# minidoxs-ctrl-lz.net
KiCad netlist of a schematic drawn in EAGLE
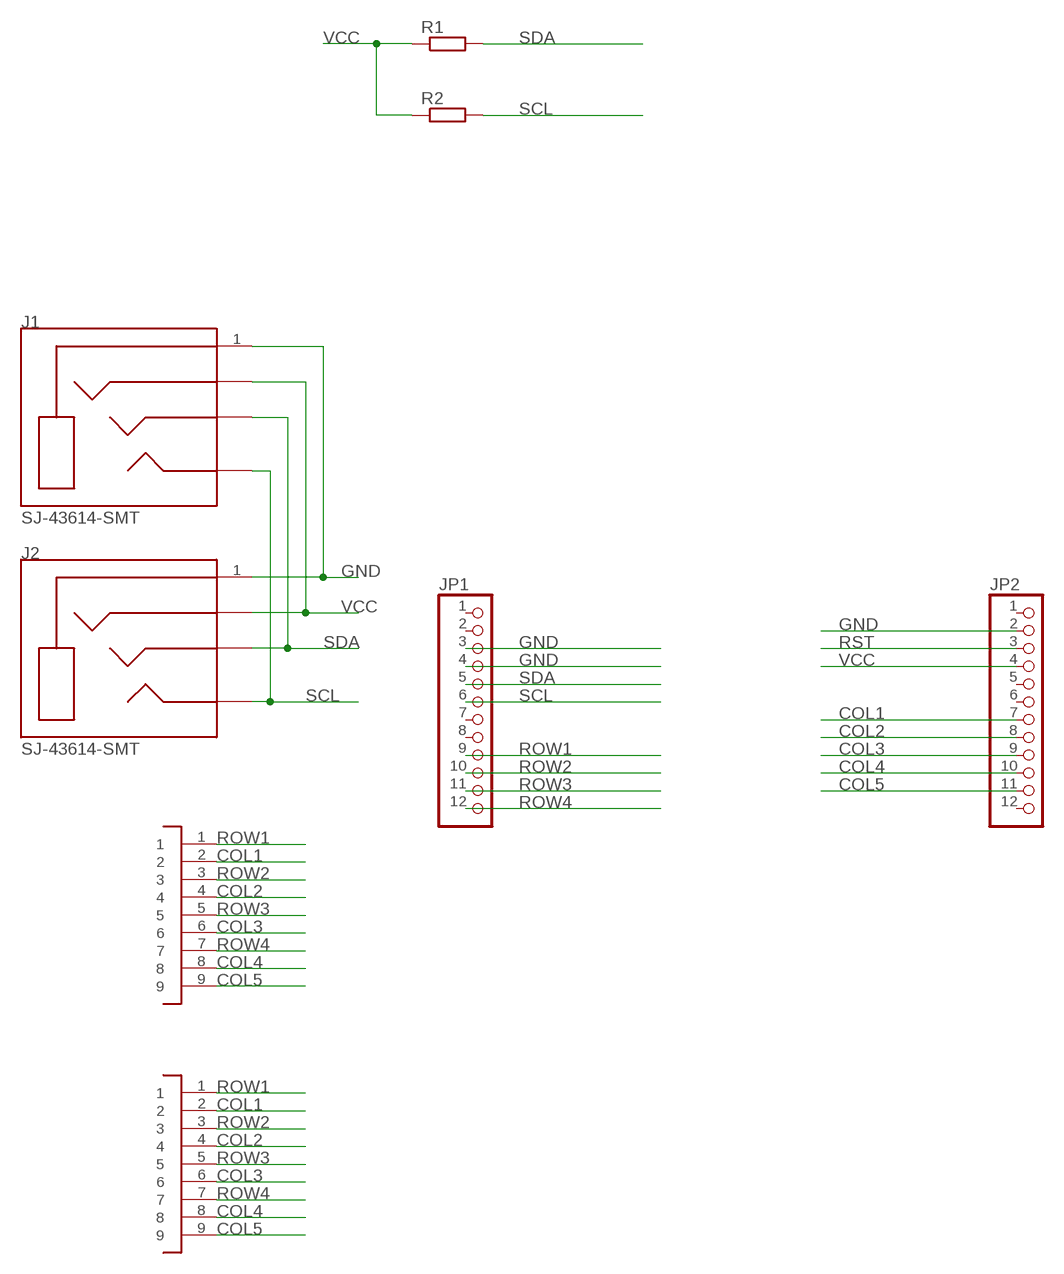
[diagram p0: schematic, sheet 1]

(export (version "E")
  (design (tool "Eeschema 10.0.6"))
  (components
    (comp (ref "J1")
      (value "SJ-43614-SMT")
      (footprint "eagle-import:CUI_SJ-43614-SMT")
      (fields (field (name "MANUFACTURER") "CUI INC"))
      (libsource (lib "eagle-import") (part "SJ-43614-SMT"))
    )
    (comp (ref "J2")
      (value "SJ-43614-SMT")
      (footprint "eagle-import:CUI_SJ-43614-SMT")
      (fields (field (name "MANUFACTURER") "CUI INC"))
      (libsource (lib "eagle-import") (part "SJ-43614-SMT"))
    )
    (comp (ref "JP1")
      (value "PINHD-1X12")
      (footprint "eagle-import:1X12")
      (libsource (lib "eagle-import") (part "PINHD-1X12"))
    )
    (comp (ref "JP2")
      (value "PINHD-1X12")
      (footprint "eagle-import:1X12")
      (libsource (lib "eagle-import") (part "PINHD-1X12"))
    )
    (comp (ref "R1")
      (value "RESISTOR-0603")
      (footprint "eagle-import:R0603")
      (libsource (lib "eagle-import") (part "RESISTOR-0603"))
    )
    (comp (ref "R2")
      (value "RESISTOR-0603")
      (footprint "eagle-import:R0603")
      (libsource (lib "eagle-import") (part "RESISTOR-0603"))
    )
    (comp (ref "U$1")
      (value "HEADER-9X1-2.54")
      (footprint "eagle-import:HEADER-9X1-2.54")
      (libsource (lib "eagle-import") (part "HEADER-9X1-2.54"))
    )
    (comp (ref "U$2")
      (value "HEADER-9X1-2.54")
      (footprint "eagle-import:HEADER-9X1-2.54")
      (libsource (lib "eagle-import") (part "HEADER-9X1-2.54"))
    )
  )
  (nets
    (net (code "1") (name "/COL1") (class "Default")
      (node (ref "JP2") (pin "7") (pinfunction "7_7") (pintype "passive"))
      (node (ref "U$1") (pin "2") (pinfunction "2_2") (pintype "bidirectional"))
      (node (ref "U$2") (pin "2") (pinfunction "2_2") (pintype "bidirectional"))
    )
    (net (code "2") (name "/COL2") (class "Default")
      (node (ref "JP2") (pin "8") (pinfunction "8_8") (pintype "passive"))
      (node (ref "U$1") (pin "4") (pinfunction "4_4") (pintype "bidirectional"))
      (node (ref "U$2") (pin "4") (pinfunction "4_4") (pintype "bidirectional"))
    )
    (net (code "3") (name "/COL3") (class "Default")
      (node (ref "JP2") (pin "9") (pinfunction "9_9") (pintype "passive"))
      (node (ref "U$1") (pin "6") (pinfunction "6_6") (pintype "bidirectional"))
      (node (ref "U$2") (pin "6") (pinfunction "6_6") (pintype "bidirectional"))
    )
    (net (code "4") (name "/COL4") (class "Default")
      (node (ref "JP2") (pin "10") (pinfunction "10_10") (pintype "passive"))
      (node (ref "U$1") (pin "8") (pinfunction "8_8") (pintype "bidirectional"))
      (node (ref "U$2") (pin "8") (pinfunction "8_8") (pintype "bidirectional"))
    )
    (net (code "5") (name "/COL5") (class "Default")
      (node (ref "JP2") (pin "11") (pinfunction "11_11") (pintype "passive"))
      (node (ref "U$1") (pin "9") (pinfunction "9_9") (pintype "bidirectional"))
      (node (ref "U$2") (pin "9") (pinfunction "9_9") (pintype "bidirectional"))
    )
    (net (code "6") (name "/GND") (class "Default")
      (node (ref "J1") (pin "1") (pinfunction "SLEEVE_1") (pintype "passive"))
      (node (ref "J2") (pin "1") (pinfunction "SLEEVE_1") (pintype "passive"))
      (node (ref "JP1") (pin "3") (pinfunction "3_3") (pintype "passive"))
      (node (ref "JP1") (pin "4") (pinfunction "4_4") (pintype "passive"))
      (node (ref "JP2") (pin "2") (pinfunction "2_2") (pintype "passive"))
    )
    (net (code "7") (name "/ROW1") (class "Default")
      (node (ref "JP1") (pin "9") (pinfunction "9_9") (pintype "passive"))
      (node (ref "U$1") (pin "1") (pinfunction "1_1") (pintype "bidirectional"))
      (node (ref "U$2") (pin "1") (pinfunction "1_1") (pintype "bidirectional"))
    )
    (net (code "8") (name "/ROW2") (class "Default")
      (node (ref "JP1") (pin "10") (pinfunction "10_10") (pintype "passive"))
      (node (ref "U$1") (pin "3") (pinfunction "3_3") (pintype "bidirectional"))
      (node (ref "U$2") (pin "3") (pinfunction "3_3") (pintype "bidirectional"))
    )
    (net (code "9") (name "/ROW3") (class "Default")
      (node (ref "JP1") (pin "11") (pinfunction "11_11") (pintype "passive"))
      (node (ref "U$1") (pin "5") (pinfunction "5_5") (pintype "bidirectional"))
      (node (ref "U$2") (pin "5") (pinfunction "5_5") (pintype "bidirectional"))
    )
    (net (code "10") (name "/ROW4") (class "Default")
      (node (ref "JP1") (pin "12") (pinfunction "12_12") (pintype "passive"))
      (node (ref "U$1") (pin "7") (pinfunction "7_7") (pintype "bidirectional"))
      (node (ref "U$2") (pin "7") (pinfunction "7_7") (pintype "bidirectional"))
    )
    (net (code "11") (name "/RST") (class "Default")
      (node (ref "JP2") (pin "3") (pinfunction "3_3") (pintype "passive"))
    )
    (net (code "12") (name "/SCL") (class "Default")
      (node (ref "J1") (pin "2") (pinfunction "TIP_2") (pintype "passive"))
      (node (ref "J2") (pin "2") (pinfunction "TIP_2") (pintype "passive"))
      (node (ref "JP1") (pin "6") (pinfunction "6_6") (pintype "passive"))
      (node (ref "R2") (pin "2") (pinfunction "2_2") (pintype "passive"))
    )
    (net (code "13") (name "/SDA") (class "Default")
      (node (ref "J1") (pin "3") (pinfunction "RING1_3") (pintype "passive"))
      (node (ref "J2") (pin "3") (pinfunction "RING1_3") (pintype "passive"))
      (node (ref "JP1") (pin "5") (pinfunction "5_5") (pintype "passive"))
      (node (ref "R1") (pin "2") (pinfunction "2_2") (pintype "passive"))
    )
    (net (code "14") (name "/VCC") (class "Default")
      (node (ref "J1") (pin "4") (pinfunction "RING2_4") (pintype "passive"))
      (node (ref "J2") (pin "4") (pinfunction "RING2_4") (pintype "passive"))
      (node (ref "JP2") (pin "4") (pinfunction "4_4") (pintype "passive"))
      (node (ref "R1") (pin "1") (pinfunction "1_1") (pintype "passive"))
      (node (ref "R2") (pin "1") (pinfunction "1_1") (pintype "passive"))
    )
    (net (code "15") (name "unconnected-(JP1-Pad1)") (class "Default")
      (node (ref "JP1") (pin "1") (pinfunction "1_1") (pintype "passive"))
    )
    (net (code "16") (name "unconnected-(JP1-Pad2)") (class "Default")
      (node (ref "JP1") (pin "2") (pinfunction "2_2") (pintype "passive"))
    )
    (net (code "17") (name "unconnected-(JP1-Pad7)") (class "Default")
      (node (ref "JP1") (pin "7") (pinfunction "7_7") (pintype "passive"))
    )
    (net (code "18") (name "unconnected-(JP1-Pad8)") (class "Default")
      (node (ref "JP1") (pin "8") (pinfunction "8_8") (pintype "passive"))
    )
    (net (code "19") (name "unconnected-(JP2-Pad1)") (class "Default")
      (node (ref "JP2") (pin "1") (pinfunction "1_1") (pintype "passive"))
    )
    (net (code "20") (name "unconnected-(JP2-Pad5)") (class "Default")
      (node (ref "JP2") (pin "5") (pinfunction "5_5") (pintype "passive"))
    )
    (net (code "21") (name "unconnected-(JP2-Pad6)") (class "Default")
      (node (ref "JP2") (pin "6") (pinfunction "6_6") (pintype "passive"))
    )
    (net (code "22") (name "unconnected-(JP2-Pad12)") (class "Default")
      (node (ref "JP2") (pin "12") (pinfunction "12_12") (pintype "passive"))
    )
  )
)
